# Peripherals.net
KiCad netlist of a schematic drawn in Altium Designer
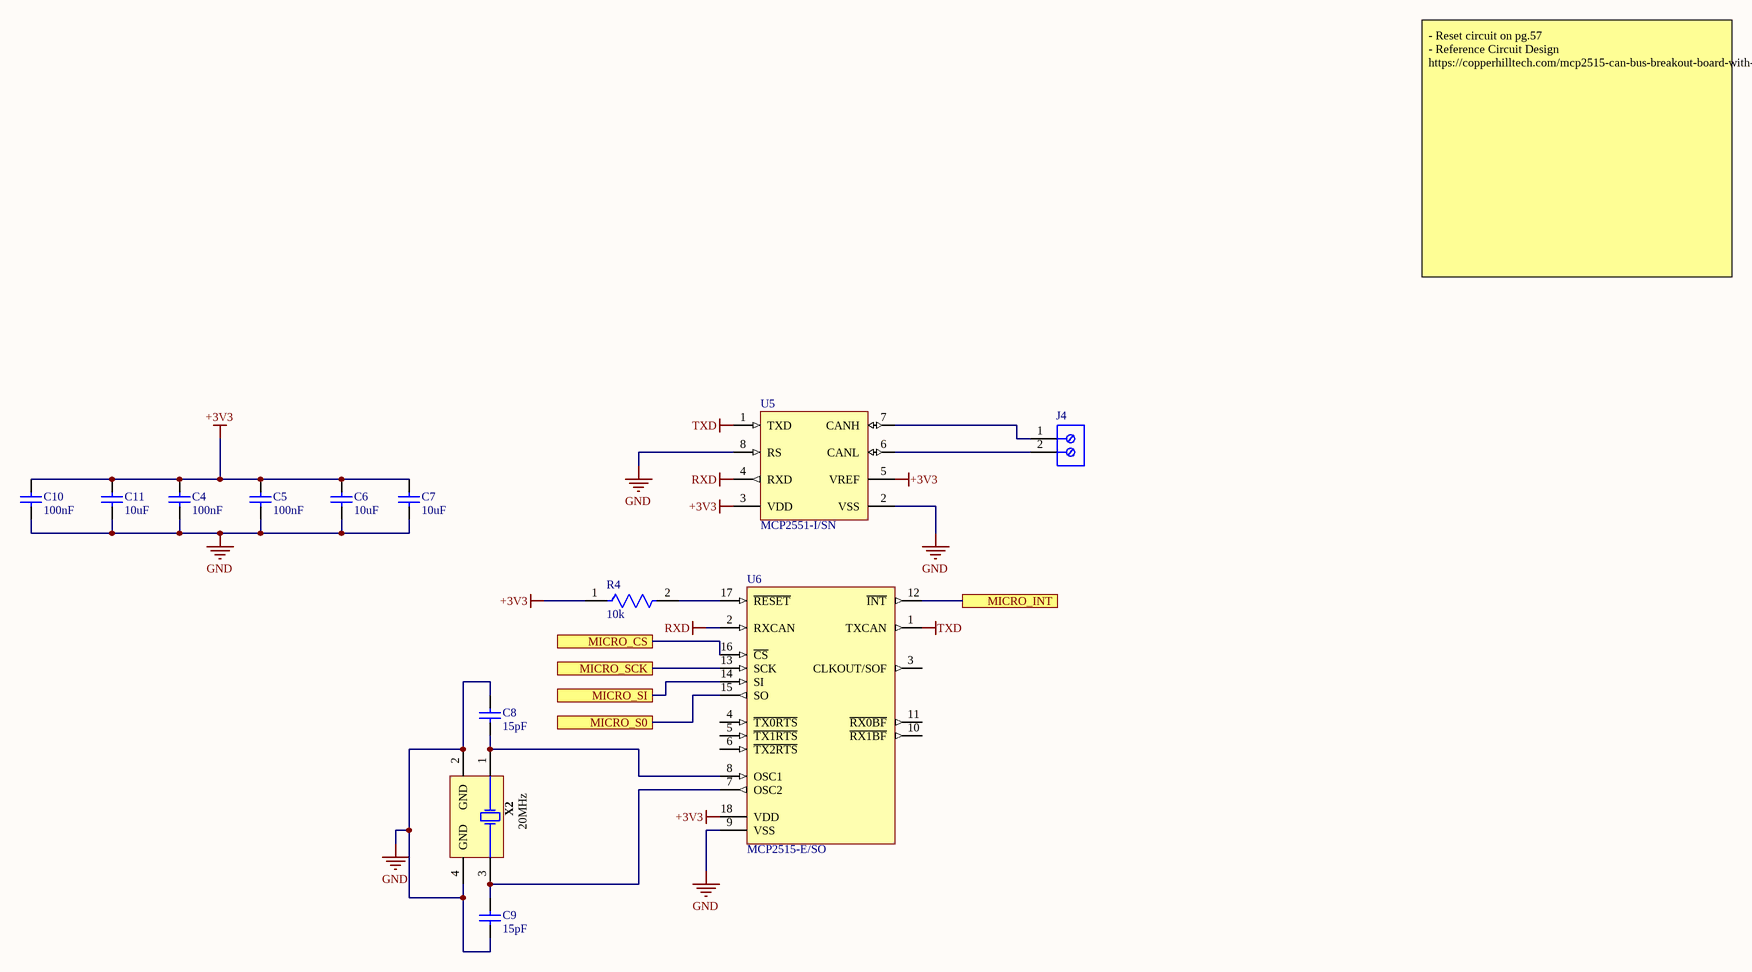
[diagram p0: Peripherals.SchDoc]

(export (version "E")
  (design (tool "Eeschema 10.0.6"))
  (components
    (comp (ref "C4")
      (value "100nF")
      (footprint "CAPC2013X94X50ML20T25")
      (fields
        (field (name "MANUFACTURER") "AVX Interconnect / Elco")
        (field (name "PART NUMBER") "08051C104JAT2A")
      )
      (libsource (lib "Altium Content Vault") (part "CAP"))
    )
    (comp (ref "C5")
      (value "100nF")
      (footprint "CAPC2013X94X50ML20T25")
      (fields
        (field (name "MANUFACTURER") "AVX Interconnect / Elco")
        (field (name "PART NUMBER") "08051C104JAT2A")
      )
      (libsource (lib "Altium Content Vault") (part "CAP"))
    )
    (comp (ref "C6")
      (value "10uF")
      (footprint "CAPC2013X115X51LL20T26")
      (fields
        (field (name "MANUFACTURER") "AVX Interconnect / Elco")
        (field (name "PART NUMBER") "08056C106KAT2A")
      )
      (libsource (lib "Altium Content Vault") (part "CAP"))
    )
    (comp (ref "C7")
      (value "10uF")
      (footprint "CAPC2013X115X51LL20T26")
      (fields
        (field (name "MANUFACTURER") "AVX Interconnect / Elco")
        (field (name "PART NUMBER") "08056C106KAT2A")
      )
      (libsource (lib "Altium Content Vault") (part "CAP"))
    )
    (comp (ref "C8")
      (value "15pF")
      (footprint "CAPC2013X94X50NL20T25")
      (fields
        (field (name "PART NUMBER") "08051A150FAT2A")
        (field (name "MANUFACTURER") "AVX Interconnect / Elco")
      )
      (libsource (lib "Altium Content Vault") (part "CAP"))
    )
    (comp (ref "C9")
      (value "15pF")
      (footprint "CAPC2013X94X50NL20T25")
      (fields
        (field (name "PART NUMBER") "08051A150FAT2A")
        (field (name "MANUFACTURER") "AVX Interconnect / Elco")
      )
      (libsource (lib "Altium Content Vault") (part "CAP"))
    )
    (comp (ref "C10")
      (value "100nF")
      (footprint "CAPC2013X94X50ML20T25")
      (fields
        (field (name "MANUFACTURER") "AVX Interconnect / Elco")
        (field (name "PART NUMBER") "08051C104JAT2A")
      )
      (libsource (lib "Altium Content Vault") (part "CAP"))
    )
    (comp (ref "C11")
      (value "10uF")
      (footprint "CAPC2013X115X51LL20T26")
      (fields
        (field (name "MANUFACTURER") "AVX Interconnect / Elco")
        (field (name "PART NUMBER") "08056C106KAT2A")
      )
      (libsource (lib "Altium Content Vault") (part "CAP"))
    )
    (comp (ref "J4")
      (value "~")
      (footprint "691214110002")
      (description "Serie 2141 - 3.50 mm Horizontal Entry Modular with Rising Cage Clamp WR-TBL, 2 pin")
      (fields
        (field (name "PART NUMBER") "691214110002")
        (field (name "MANUFACTURER") "Wurth Elektronik")
        (field (name "PUBLISHER") "WurthElektronik")
      )
      (libsource (lib "Altium Content Vault") (part "WE-CN-1P-F-TB2"))
    )
    (comp (ref "R4")
      (value "10k")
      (footprint "FP-AC0805-MFG")
      (description "RES SMD 10K OHM 1% 1/8W 0805")
      (fields
        (field (name "OCTOPART") "https://octopart.com/ac0805fr-0710kl-yageo-21711112")
        (field (name "MANUFACTURER PART NUMBER") "AC0805FR-0710KL")
      )
      (libsource (lib "Altium Content Vault") (part "1029c3af85768c4190bb7ad29bc67b5"))
    )
    (comp (ref "U5")
      (value "MCP2551-I/SN")
      (footprint "MCHP-SN8_V")
      (fields (field (name "MANUFACTURER") "Microchip"))
      (libsource (lib "Altium Content Vault") (part "MCHP-MCP2551-SN8"))
    )
    (comp (ref "U6")
      (value "MCP2515-E/SO")
      (footprint "SOIC-SO18_M")
      (description "Stand-Alone CAN Controller With SPI Interface, 18-Pin SOIC, Extended Temperature")
      (libsource (lib "Altium Content Vault") (part "COM-CAN-MCP2515-18"))
    )
    (comp (ref "X2")
      (value "20MHz")
      (footprint "TXC-7B-4_V")
      (libsource (lib "Altium Content Vault") (part "XTAL-1-3-4"))
    )
  )
  (nets
    (net (code "1") (name "+3V3") (class "Default")
      (node (ref "C10") (pin "2") (pinfunction "2_2") (pintype "passive"))
      (node (ref "C11") (pin "2") (pinfunction "2_2") (pintype "passive"))
      (node (ref "C4") (pin "2") (pinfunction "2_2") (pintype "passive"))
      (node (ref "C5") (pin "2") (pinfunction "2_2") (pintype "passive"))
      (node (ref "C6") (pin "2") (pinfunction "2_2") (pintype "passive"))
      (node (ref "C7") (pin "2") (pinfunction "2_2") (pintype "passive"))
      (node (ref "R4") (pin "1") (pinfunction "1_1") (pintype "passive"))
      (node (ref "U5") (pin "3") (pinfunction "VDD_3") (pintype "power_in"))
      (node (ref "U5") (pin "5") (pinfunction "VREF_5") (pintype "power_in"))
      (node (ref "U6") (pin "18") (pinfunction "VDD_18") (pintype "power_in"))
    )
    (net (code "2") (name "/MICRO_CS") (class "Default")
      (node (ref "U6") (pin "16") (pinfunction "~{CS}_16") (pintype "input"))
    )
    (net (code "3") (name "/MICRO_INT") (class "Default")
      (node (ref "U6") (pin "12") (pinfunction "~{INT}_12") (pintype "output"))
    )
    (net (code "4") (name "/MICRO_S0") (class "Default")
      (node (ref "U6") (pin "15") (pinfunction "SO_15") (pintype "output"))
    )
    (net (code "5") (name "/MICRO_SCK") (class "Default")
      (node (ref "U6") (pin "13") (pinfunction "SCK_13") (pintype "input"))
    )
    (net (code "6") (name "/MICRO_SI") (class "Default")
      (node (ref "U6") (pin "14") (pinfunction "SI_14") (pintype "input"))
    )
    (net (code "7") (name "GND") (class "Default")
      (node (ref "C10") (pin "1") (pinfunction "1_1") (pintype "passive"))
      (node (ref "C11") (pin "1") (pinfunction "1_1") (pintype "passive"))
      (node (ref "C4") (pin "1") (pinfunction "1_1") (pintype "passive"))
      (node (ref "C5") (pin "1") (pinfunction "1_1") (pintype "passive"))
      (node (ref "C6") (pin "1") (pinfunction "1_1") (pintype "passive"))
      (node (ref "C7") (pin "1") (pinfunction "1_1") (pintype "passive"))
      (node (ref "C8") (pin "2") (pinfunction "2_2") (pintype "passive"))
      (node (ref "C9") (pin "1") (pinfunction "1_1") (pintype "passive"))
      (node (ref "U5") (pin "2") (pinfunction "VSS_2") (pintype "power_in"))
      (node (ref "U5") (pin "8") (pinfunction "RS_8") (pintype "input"))
      (node (ref "U6") (pin "9") (pinfunction "VSS_9") (pintype "power_in"))
      (node (ref "X2") (pin "2") (pinfunction "GND_2") (pintype "power_in"))
      (node (ref "X2") (pin "4") (pinfunction "GND_4") (pintype "power_in"))
    )
    (net (code "8") (name "Net-(U5-CANH)") (class "Default")
      (node (ref "J4") (pin "1") (pinfunction "1_1") (pintype "passive"))
      (node (ref "U5") (pin "7") (pinfunction "CANH_7") (pintype "bidirectional"))
    )
    (net (code "9") (name "Net-(U5-CANL)") (class "Default")
      (node (ref "J4") (pin "2") (pinfunction "2_2") (pintype "passive"))
      (node (ref "U5") (pin "6") (pinfunction "CANL_6") (pintype "bidirectional"))
    )
    (net (code "10") (name "Net-(U6-OSC1)") (class "Default")
      (node (ref "C8") (pin "1") (pinfunction "1_1") (pintype "passive"))
      (node (ref "U6") (pin "8") (pinfunction "OSC1_8") (pintype "input"))
      (node (ref "X2") (pin "1") (pinfunction "X1_1") (pintype "passive"))
    )
    (net (code "11") (name "Net-(U6-OSC2)") (class "Default")
      (node (ref "C9") (pin "2") (pinfunction "2_2") (pintype "passive"))
      (node (ref "U6") (pin "7") (pinfunction "OSC2_7") (pintype "output"))
      (node (ref "X2") (pin "3") (pinfunction "X2_3") (pintype "passive"))
    )
    (net (code "12") (name "Net-(U6-~{RESET})") (class "Default")
      (node (ref "R4") (pin "2") (pinfunction "2_2") (pintype "passive"))
      (node (ref "U6") (pin "17") (pinfunction "~{RESET}_17") (pintype "input"))
    )
    (net (code "13") (name "RXD") (class "Default")
      (node (ref "U5") (pin "4") (pinfunction "RXD_4") (pintype "output"))
      (node (ref "U6") (pin "2") (pinfunction "RXCAN_2") (pintype "input"))
    )
    (net (code "14") (name "TXD") (class "Default")
      (node (ref "U5") (pin "1") (pinfunction "TXD_1") (pintype "input"))
      (node (ref "U6") (pin "1") (pinfunction "TXCAN_1") (pintype "output"))
    )
    (net (code "15") (name "unconnected-(U6-CLKOUT{slash}SOF-Pad3)") (class "Default")
      (node (ref "U6") (pin "3") (pinfunction "CLKOUT/SOF_3") (pintype "output"))
    )
    (net (code "16") (name "unconnected-(U6-~{RX0BF}-Pad11)") (class "Default")
      (node (ref "U6") (pin "11") (pinfunction "~{RX0BF}_11") (pintype "output"))
    )
    (net (code "17") (name "unconnected-(U6-~{RX1BF}-Pad10)") (class "Default")
      (node (ref "U6") (pin "10") (pinfunction "~{RX1BF}_10") (pintype "output"))
    )
    (net (code "18") (name "unconnected-(U6-~{TX0RTS}-Pad4)") (class "Default")
      (node (ref "U6") (pin "4") (pinfunction "~{TX0RTS}_4") (pintype "input"))
    )
    (net (code "19") (name "unconnected-(U6-~{TX1RTS}-Pad5)") (class "Default")
      (node (ref "U6") (pin "5") (pinfunction "~{TX1RTS}_5") (pintype "input"))
    )
    (net (code "20") (name "unconnected-(U6-~{TX2RTS}-Pad6)") (class "Default")
      (node (ref "U6") (pin "6") (pinfunction "~{TX2RTS}_6") (pintype "input"))
    )
  )
)
